# 03_Power_Spply.net
KiCad netlist of a schematic drawn in Altium Designer
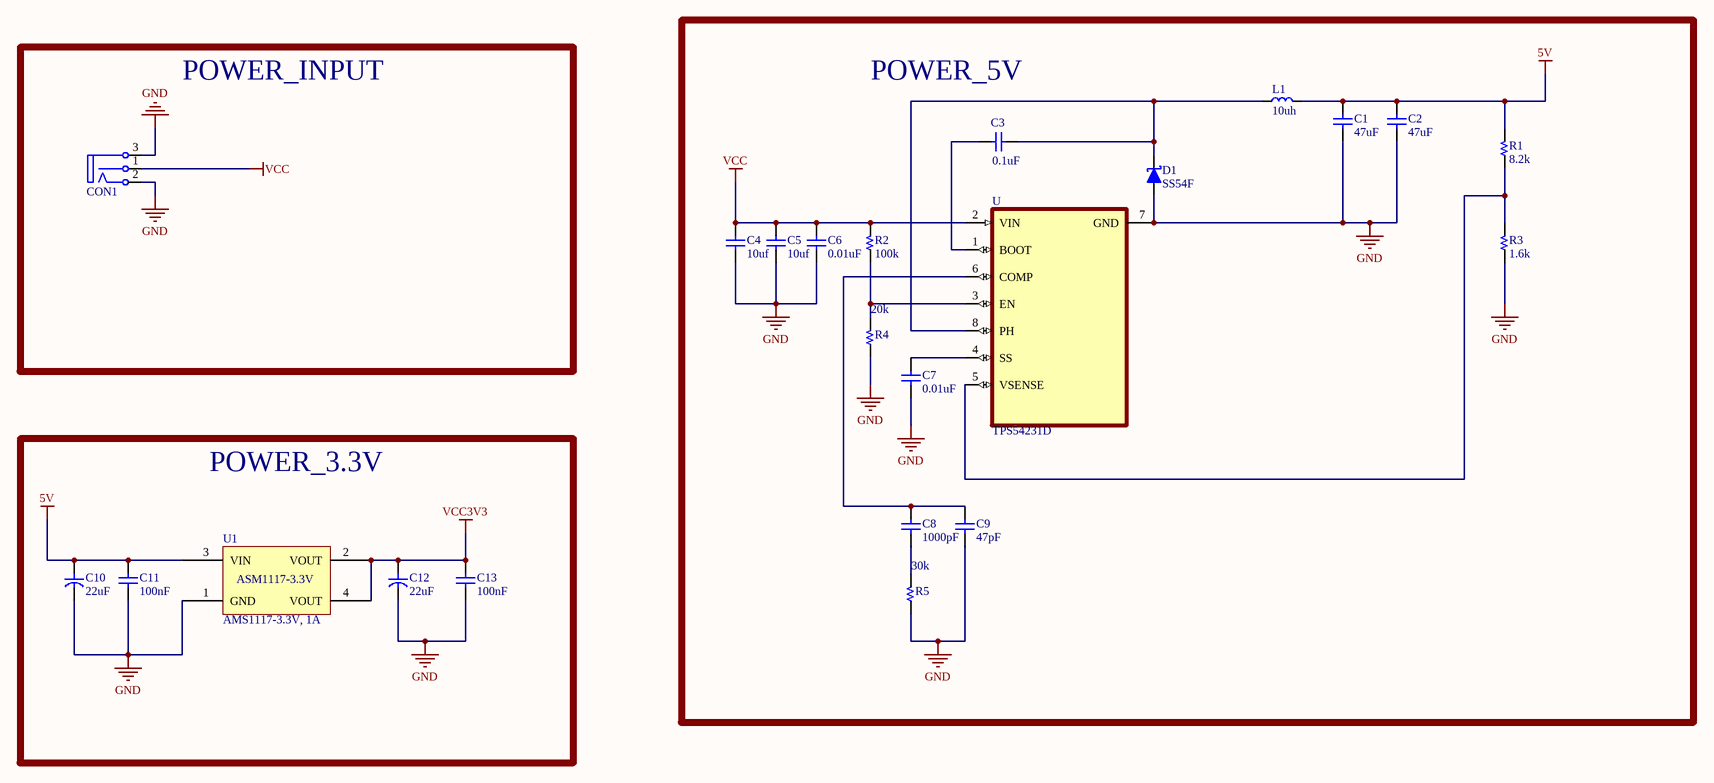
[diagram p0: 03_Power_Spply.SchDoc]

(export (version "E")
  (design (tool "Eeschema 10.0.6"))
  (components
    (comp (ref "C1")
      (value "47uF")
      (footprint "C 0805")
      (description "Capacitor non-pol")
      (libsource (lib "chipfc_libs") (part "Capacitor NP"))
    )
    (comp (ref "C2")
      (value "47uF")
      (footprint "C 0805")
      (description "Capacitor non-pol")
      (libsource (lib "chipfc_libs") (part "Capacitor NP"))
    )
    (comp (ref "C3")
      (value "0.1uF")
      (footprint "C 0805")
      (description "Capacitor non-pol")
      (libsource (lib "chipfc_libs") (part "Capacitor NP"))
    )
    (comp (ref "C4")
      (value "10uf")
      (footprint "C 0805")
      (description "Capacitor non-pol")
      (libsource (lib "chipfc_libs") (part "Capacitor NP"))
    )
    (comp (ref "C5")
      (value "10uf")
      (footprint "C 0805")
      (description "Capacitor non-pol")
      (libsource (lib "chipfc_libs") (part "Capacitor NP"))
    )
    (comp (ref "C6")
      (value "0.01uF")
      (footprint "C 0805")
      (description "Capacitor non-pol")
      (libsource (lib "chipfc_libs") (part "Capacitor NP"))
    )
    (comp (ref "C7")
      (value "0.01uF")
      (footprint "C 0805")
      (description "Capacitor non-pol")
      (libsource (lib "chipfc_libs") (part "Capacitor NP"))
    )
    (comp (ref "C8")
      (value "1000pF")
      (footprint "C 0805")
      (description "Capacitor non-pol")
      (libsource (lib "chipfc_libs") (part "Capacitor NP"))
    )
    (comp (ref "C9")
      (value "47pF")
      (footprint "C 0805")
      (description "Capacitor non-pol")
      (libsource (lib "chipfc_libs") (part "Capacitor NP"))
    )
    (comp (ref "C10")
      (value "22uF")
      (footprint "C SMD TAN 2312 (C)")
      (description "Capacitor pol")
      (libsource (lib "chipfc_libs") (part "Capacitor"))
    )
    (comp (ref "C11")
      (value "100nF")
      (footprint "C 0805")
      (description "Capacitor non-pol")
      (libsource (lib "chipfc_libs") (part "Capacitor NP"))
    )
    (comp (ref "C12")
      (value "22uF")
      (footprint "C SMD TAN 2312 (C)")
      (description "Capacitor pol")
      (libsource (lib "chipfc_libs") (part "Capacitor"))
    )
    (comp (ref "C13")
      (value "100nF")
      (footprint "C 0805")
      (description "Capacitor non-pol")
      (libsource (lib "chipfc_libs") (part "Capacitor NP"))
    )
    (comp (ref "CON1")
      (value "CON DC PWR")
      (footprint "CONN/DC/PWR/5.0MM")
      (description "DC input connector")
      (libsource (lib "connectors") (part "CON DC PWR"))
    )
    (comp (ref "D1")
      (value "SS54F")
      (footprint "DO-214AC (SMA)")
      (description "Schottky Diode")
      (libsource (lib "chipfc_libs") (part "Diode Schottky"))
    )
    (comp (ref "L1")
      (value "10uh")
      (footprint "Inductor SMD CDRH3D67")
      (description "Inductor")
      (libsource (lib "chipfc_libs") (part "Inductor"))
    )
    (comp (ref "R1")
      (value "8.2k")
      (footprint "R 0805")
      (description "Resistor")
      (libsource (lib "chipfc_libs") (part "Resistor"))
    )
    (comp (ref "R2")
      (value "100k")
      (footprint "R 0805")
      (description "Resistor")
      (libsource (lib "chipfc_libs") (part "Resistor"))
    )
    (comp (ref "R3")
      (value "1.6k")
      (footprint "R 0805")
      (description "Resistor")
      (libsource (lib "chipfc_libs") (part "Resistor"))
    )
    (comp (ref "R4")
      (value "20k")
      (footprint "R 0805")
      (description "Resistor")
      (libsource (lib "chipfc_libs") (part "Resistor"))
    )
    (comp (ref "R5")
      (value "30k")
      (footprint "R 0805")
      (description "Resistor")
      (libsource (lib "chipfc_libs") (part "Resistor"))
    )
    (comp (ref "U")
      (value "TPS54231D")
      (footprint "SOIC127P599X175-8N")
      (description "å…·æœ‰Eco-modeï¼†tradeçš„3.5è‡³28Vè¾“å…¥ï¼Œ2Aï¼Œ570kHzé™åŽ‹è½¬æ¢å™¨ï¼›8-SOIC -40è‡³150")
      (fields (field (name "MF") "Texas Instruments"))
      (libsource (lib "TPS54231D") (part "TPS54231D"))
    )
    (comp (ref "U1")
      (value "AMS1117-3.3V, 1A")
      (footprint "AMS1117-3.3V SOT223")
      (description "1A 60dB@(120Hz) Fixed 3.3V Positive electrode 12V SOT-223 Linear Voltage Regulators (LDO) ROHS")
      (fields (field (name "MANUFACTURER") "AMS") (field (name "LCSC PART #") "C347222"))
      (libsource (lib "AMS_family") (part "AMS1117-3.3V"))
    )
  )
  (nets
    (net (code "1") (name "5V") (class "Default")
      (node (ref "C1") (pin "2") (pinfunction "2_2") (pintype "passive"))
      (node (ref "C10") (pin "1") (pinfunction "1_1") (pintype "passive"))
      (node (ref "C11") (pin "2") (pinfunction "2_2") (pintype "passive"))
      (node (ref "C2") (pin "2") (pinfunction "2_2") (pintype "passive"))
      (node (ref "L1") (pin "2") (pinfunction "2_2") (pintype "passive"))
      (node (ref "R1") (pin "2") (pinfunction "2_2") (pintype "passive"))
      (node (ref "U1") (pin "3") (pinfunction "VIN_3") (pintype "passive"))
    )
    (net (code "2") (name "GND") (class "Default")
      (node (ref "C1") (pin "1") (pinfunction "1_1") (pintype "passive"))
      (node (ref "C10") (pin "2") (pinfunction "2_2") (pintype "passive"))
      (node (ref "C11") (pin "1") (pinfunction "1_1") (pintype "passive"))
      (node (ref "C12") (pin "2") (pinfunction "2_2") (pintype "passive"))
      (node (ref "C13") (pin "1") (pinfunction "1_1") (pintype "passive"))
      (node (ref "C2") (pin "1") (pinfunction "1_1") (pintype "passive"))
      (node (ref "C4") (pin "1") (pinfunction "1_1") (pintype "passive"))
      (node (ref "C5") (pin "1") (pinfunction "1_1") (pintype "passive"))
      (node (ref "C6") (pin "1") (pinfunction "1_1") (pintype "passive"))
      (node (ref "C7") (pin "1") (pinfunction "1_1") (pintype "passive"))
      (node (ref "C9") (pin "1") (pinfunction "1_1") (pintype "passive"))
      (node (ref "CON1") (pin "2") (pinfunction "T_2") (pintype "passive"))
      (node (ref "CON1") (pin "3") (pinfunction "TN_3") (pintype "passive"))
      (node (ref "D1") (pin "1") (pinfunction "A_1") (pintype "passive"))
      (node (ref "R3") (pin "1") (pinfunction "1_1") (pintype "passive"))
      (node (ref "R4") (pin "1") (pinfunction "1_1") (pintype "passive"))
      (node (ref "R5") (pin "1") (pinfunction "1_1") (pintype "passive"))
      (node (ref "U") (pin "7") (pinfunction "GND_7") (pintype "power_in"))
      (node (ref "U1") (pin "1") (pinfunction "GND_1") (pintype "power_in"))
    )
    (net (code "3") (name "Net-(C8-Pad1)") (class "Default")
      (node (ref "C8") (pin "1") (pinfunction "1_1") (pintype "passive"))
      (node (ref "R5") (pin "2") (pinfunction "2_2") (pintype "passive"))
    )
    (net (code "4") (name "Net-(D1-K)") (class "Default")
      (node (ref "C3") (pin "1") (pinfunction "1_1") (pintype "passive"))
      (node (ref "D1") (pin "2") (pinfunction "K_2") (pintype "passive"))
      (node (ref "L1") (pin "1") (pinfunction "1_1") (pintype "passive"))
      (node (ref "U") (pin "8") (pinfunction "PH_8") (pintype "bidirectional"))
    )
    (net (code "5") (name "Net-(U-BOOT)") (class "Default")
      (node (ref "C3") (pin "2") (pinfunction "2_2") (pintype "passive"))
      (node (ref "U") (pin "1") (pinfunction "BOOT_1") (pintype "bidirectional"))
    )
    (net (code "6") (name "Net-(U-COMP)") (class "Default")
      (node (ref "C8") (pin "2") (pinfunction "2_2") (pintype "passive"))
      (node (ref "C9") (pin "2") (pinfunction "2_2") (pintype "passive"))
      (node (ref "U") (pin "6") (pinfunction "COMP_6") (pintype "bidirectional"))
    )
    (net (code "7") (name "Net-(U-EN)") (class "Default")
      (node (ref "R2") (pin "1") (pinfunction "1_1") (pintype "passive"))
      (node (ref "R4") (pin "2") (pinfunction "2_2") (pintype "passive"))
      (node (ref "U") (pin "3") (pinfunction "EN_3") (pintype "bidirectional"))
    )
    (net (code "8") (name "Net-(U-SS)") (class "Default")
      (node (ref "C7") (pin "2") (pinfunction "2_2") (pintype "passive"))
      (node (ref "U") (pin "4") (pinfunction "SS_4") (pintype "bidirectional"))
    )
    (net (code "9") (name "Net-(U-VSENSE)") (class "Default")
      (node (ref "R1") (pin "1") (pinfunction "1_1") (pintype "passive"))
      (node (ref "R3") (pin "2") (pinfunction "2_2") (pintype "passive"))
      (node (ref "U") (pin "5") (pinfunction "VSENSE_5") (pintype "bidirectional"))
    )
    (net (code "10") (name "VCC") (class "Default")
      (node (ref "C4") (pin "2") (pinfunction "2_2") (pintype "passive"))
      (node (ref "C5") (pin "2") (pinfunction "2_2") (pintype "passive"))
      (node (ref "C6") (pin "2") (pinfunction "2_2") (pintype "passive"))
      (node (ref "CON1") (pin "1") (pinfunction "S_1") (pintype "power_in"))
      (node (ref "R2") (pin "2") (pinfunction "2_2") (pintype "passive"))
      (node (ref "U") (pin "2") (pinfunction "VIN_2") (pintype "input"))
    )
    (net (code "11") (name "VCC3V3") (class "Default")
      (node (ref "C12") (pin "1") (pinfunction "1_1") (pintype "passive"))
      (node (ref "C13") (pin "2") (pinfunction "2_2") (pintype "passive"))
      (node (ref "U1") (pin "2") (pinfunction "VOUT_2") (pintype "passive"))
      (node (ref "U1") (pin "4") (pinfunction "VOUT_4") (pintype "power_in"))
    )
  )
)
